# V2.net
KiCad netlist of a schematic drawn in Altium Designer
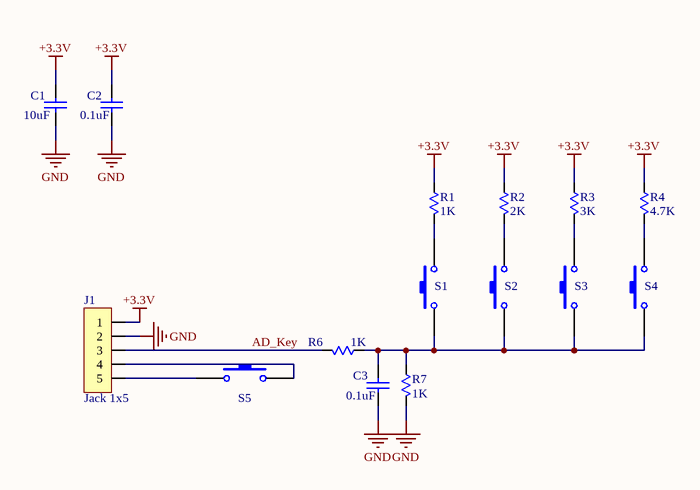
[diagram p0: 海关全向控制器按键板V2.SchDoc]

(export (version "E")
  (design (tool "Eeschema 10.0.6"))
  (components
    (comp (ref "C1")
      (value "10uF")
      (footprint "C0603")
      (description "CAP")
      (fields (field (name "PUBLISHER") "Altium Limited"))
      (libsource (lib "Passive Components Class") (part "CAP"))
    )
    (comp (ref "C2")
      (value "0.1uF")
      (footprint "C0603")
      (description "CAP")
      (fields (field (name "PUBLISHER") "Altium Limited"))
      (libsource (lib "Passive Components Class") (part "CAP"))
    )
    (comp (ref "C3")
      (value "0.1uF")
      (footprint "C0603")
      (description "CAP")
      (fields (field (name "PUBLISHER") "Altium Limited"))
      (libsource (lib "Passive Components Class") (part "CAP"))
    )
    (comp (ref "J1")
      (value "Jack 1x5")
      (footprint "ZH-5AWD")
      (description "插座")
      (libsource (lib "Connector") (part "Jack 1x5"))
    )
    (comp (ref "R1")
      (value "1K")
      (footprint "R0603")
      (description "Resistor")
      (fields (field (name "PUBLISHER") "Altium Limited"))
      (libsource (lib "Temp") (part "Res"))
    )
    (comp (ref "R2")
      (value "2K")
      (footprint "R0603")
      (description "Resistor")
      (fields (field (name "PUBLISHER") "Altium Limited"))
      (libsource (lib "Temp") (part "Res"))
    )
    (comp (ref "R3")
      (value "3K")
      (footprint "R0603")
      (description "Resistor")
      (fields (field (name "PUBLISHER") "Altium Limited"))
      (libsource (lib "Temp") (part "Res"))
    )
    (comp (ref "R4")
      (value "4.7K")
      (footprint "R0603")
      (description "Resistor")
      (fields (field (name "PUBLISHER") "Altium Limited"))
      (libsource (lib "Temp") (part "Res"))
    )
    (comp (ref "R6")
      (value "1K")
      (footprint "R0603")
      (description "Resistor")
      (fields (field (name "PUBLISHER") "Altium Limited"))
      (libsource (lib "Temp") (part "Res"))
    )
    (comp (ref "R7")
      (value "1K")
      (footprint "R0603")
      (description "Resistor")
      (fields (field (name "PUBLISHER") "Altium Limited"))
      (libsource (lib "Temp") (part "Res"))
    )
    (comp (ref "S1")
      (value "SW-PB")
      (footprint "SW3X6X5")
      (description "Switch")
      (fields (field (name "PUBLISHER") "Altium Limited"))
      (libsource (lib "Miscellaneous Devices") (part "SW-PB"))
    )
    (comp (ref "S2")
      (value "SW-PB")
      (footprint "SW3X6X5")
      (description "Switch")
      (fields (field (name "PUBLISHER") "Altium Limited"))
      (libsource (lib "Miscellaneous Devices") (part "SW-PB"))
    )
    (comp (ref "S3")
      (value "SW-PB")
      (footprint "SW3X6X5")
      (description "Switch")
      (fields (field (name "PUBLISHER") "Altium Limited"))
      (libsource (lib "Miscellaneous Devices") (part "SW-PB"))
    )
    (comp (ref "S4")
      (value "SW-PB")
      (footprint "SW3X6X5")
      (description "Switch")
      (fields (field (name "PUBLISHER") "Altium Limited"))
      (libsource (lib "Miscellaneous Devices") (part "SW-PB"))
    )
    (comp (ref "S5")
      (value "SW-PB")
      (footprint "SW3X6X5")
      (description "Switch")
      (fields (field (name "PUBLISHER") "Altium Limited"))
      (libsource (lib "Miscellaneous Devices") (part "SW-PB"))
    )
  )
  (nets
    (net (code "1") (name "+3.3V") (class "Default")
      (node (ref "C1") (pin "2") (pinfunction "2_2") (pintype "passive"))
      (node (ref "C2") (pin "2") (pinfunction "2_2") (pintype "passive"))
      (node (ref "J1") (pin "1") (pinfunction "1_1") (pintype "passive"))
      (node (ref "R1") (pin "2") (pinfunction "2_2") (pintype "passive"))
      (node (ref "R2") (pin "2") (pinfunction "2_2") (pintype "passive"))
      (node (ref "R3") (pin "2") (pinfunction "2_2") (pintype "passive"))
      (node (ref "R4") (pin "2") (pinfunction "2_2") (pintype "passive"))
    )
    (net (code "2") (name "/AD_Key") (class "Default")
      (node (ref "J1") (pin "3") (pinfunction "3_3") (pintype "passive"))
      (node (ref "R6") (pin "1") (pinfunction "1_1") (pintype "passive"))
    )
    (net (code "3") (name "GND") (class "Default")
      (node (ref "C1") (pin "1") (pinfunction "1_1") (pintype "passive"))
      (node (ref "C2") (pin "1") (pinfunction "1_1") (pintype "passive"))
      (node (ref "C3") (pin "1") (pinfunction "1_1") (pintype "passive"))
      (node (ref "J1") (pin "2") (pinfunction "2_2") (pintype "passive"))
      (node (ref "R7") (pin "1") (pinfunction "1_1") (pintype "passive"))
    )
    (net (code "4") (name "Net-(C3-Pad2)") (class "Default")
      (node (ref "C3") (pin "2") (pinfunction "2_2") (pintype "passive"))
      (node (ref "R6") (pin "2") (pinfunction "2_2") (pintype "passive"))
      (node (ref "R7") (pin "2") (pinfunction "2_2") (pintype "passive"))
      (node (ref "S1") (pin "1") (pinfunction "1_1") (pintype "passive"))
      (node (ref "S2") (pin "1") (pinfunction "1_1") (pintype "passive"))
      (node (ref "S3") (pin "1") (pinfunction "1_1") (pintype "passive"))
      (node (ref "S4") (pin "1") (pinfunction "1_1") (pintype "passive"))
    )
    (net (code "5") (name "Net-(J1-Pad4)") (class "Default")
      (node (ref "J1") (pin "4") (pinfunction "4_4") (pintype "passive"))
      (node (ref "S5") (pin "2") (pinfunction "2_2") (pintype "passive"))
    )
    (net (code "6") (name "Net-(J1-Pad5)") (class "Default")
      (node (ref "J1") (pin "5") (pinfunction "5_5") (pintype "passive"))
      (node (ref "S5") (pin "1") (pinfunction "1_1") (pintype "passive"))
    )
    (net (code "7") (name "Net-(R1-Pad1)") (class "Default")
      (node (ref "R1") (pin "1") (pinfunction "1_1") (pintype "passive"))
      (node (ref "S1") (pin "2") (pinfunction "2_2") (pintype "passive"))
    )
    (net (code "8") (name "Net-(R2-Pad1)") (class "Default")
      (node (ref "R2") (pin "1") (pinfunction "1_1") (pintype "passive"))
      (node (ref "S2") (pin "2") (pinfunction "2_2") (pintype "passive"))
    )
    (net (code "9") (name "Net-(R3-Pad1)") (class "Default")
      (node (ref "R3") (pin "1") (pinfunction "1_1") (pintype "passive"))
      (node (ref "S3") (pin "2") (pinfunction "2_2") (pintype "passive"))
    )
    (net (code "10") (name "Net-(R4-Pad1)") (class "Default")
      (node (ref "R4") (pin "1") (pinfunction "1_1") (pintype "passive"))
      (node (ref "S4") (pin "2") (pinfunction "2_2") (pintype "passive"))
    )
  )
)
